# EtnaNode0_2.net
KiCad netlist of a schematic drawn in EAGLE
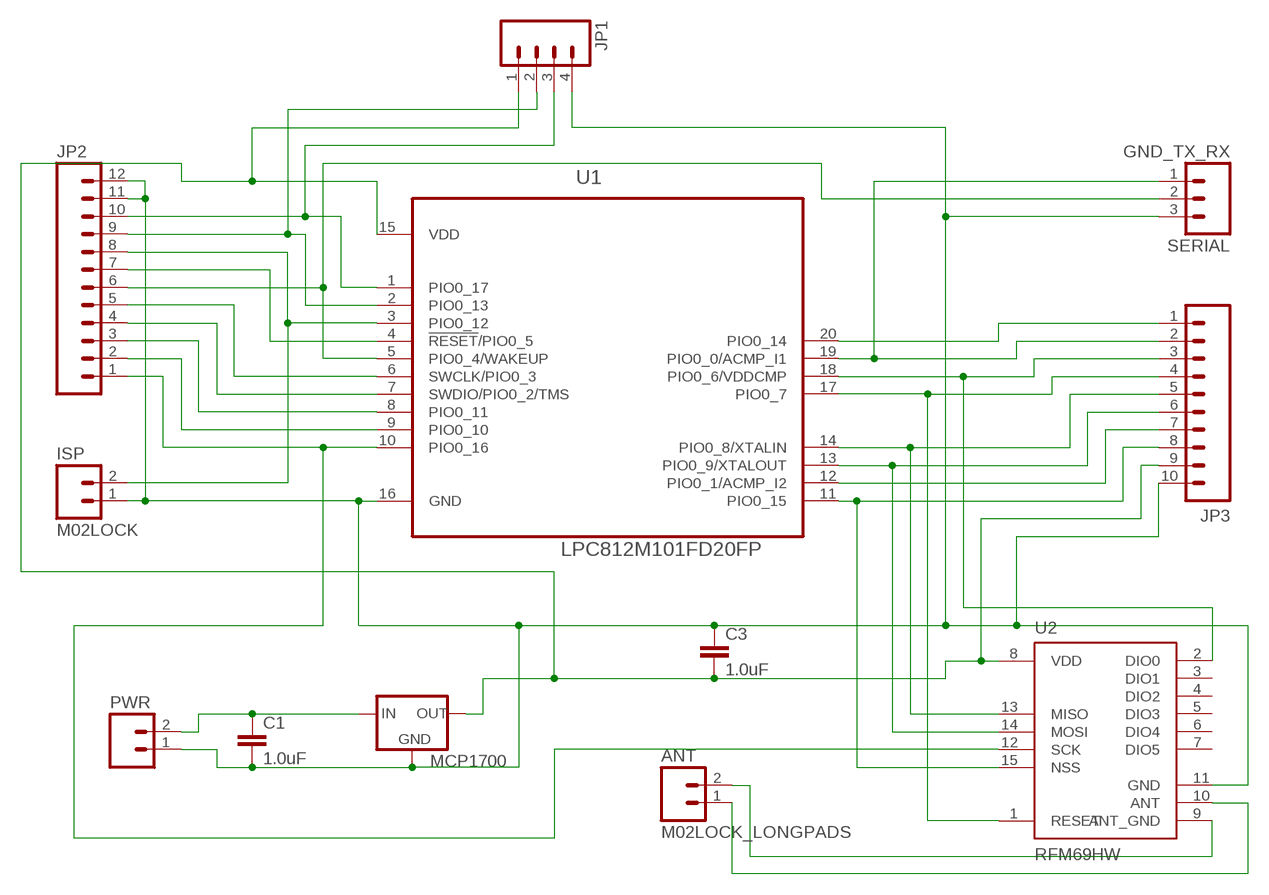
[diagram p0: schematic, sheet 1]

(export (version "E")
  (design (tool "Eeschema 10.0.6"))
  (components
    (comp (ref "ANT")
      (value "M02LOCK_LONGPADS")
      (footprint "eagle-import:1X02_LOCK_LONGPADS")
      (libsource (lib "eagle-import") (part "M02LOCK_LONGPADS"))
    )
    (comp (ref "C1")
      (value "1.0uF")
      (footprint "eagle-import:CAP-PTH-SMALL")
      (libsource (lib "eagle-import") (part "CAPPTH"))
    )
    (comp (ref "C3")
      (value "1.0uF")
      (footprint "eagle-import:CAP-PTH-SMALL")
      (libsource (lib "eagle-import") (part "CAPPTH"))
    )
    (comp (ref "ISP")
      (value "M02LOCK")
      (footprint "eagle-import:1X02_LOCK")
      (libsource (lib "eagle-import") (part "M02LOCK"))
    )
    (comp (ref "JP1")
      (value "M04LOCK")
      (footprint "eagle-import:1X04_LOCK")
      (libsource (lib "eagle-import") (part "M04LOCK"))
    )
    (comp (ref "JP2")
      (value "M12LOCK")
      (footprint "eagle-import:1X12_LOCK")
      (libsource (lib "eagle-import") (part "M12LOCK"))
    )
    (comp (ref "JP3")
      (value "M10LOCK")
      (footprint "eagle-import:1X10_LOCK")
      (libsource (lib "eagle-import") (part "M10LOCK"))
    )
    (comp (ref "MCP1700")
      (value "MCP1700INLINE")
      (footprint "eagle-import:TO92-INLINE")
      (libsource (lib "eagle-import") (part "MCP1700INLINE"))
    )
    (comp (ref "PWR")
      (value "M02LOCK_LONGPADS")
      (footprint "eagle-import:1X02_LOCK_LONGPADS")
      (libsource (lib "eagle-import") (part "M02LOCK_LONGPADS"))
    )
    (comp (ref "SERIAL")
      (value "GND_TX_RX")
      (footprint "eagle-import:1X03_LOCK")
      (libsource (lib "eagle-import") (part "M03LOCK"))
    )
    (comp (ref "U1")
      (value "LPC812M101FD20FP")
      (footprint "eagle-import:SOIC127P1032X265-20N")
      (libsource (lib "eagle-import") (part "LPC812M101FD20FP"))
    )
    (comp (ref "U2")
      (value "RFM69HW")
      (footprint "eagle-import:RFM69W-XXXS2")
      (libsource (lib "eagle-import") (part "RFM69HW"))
    )
  )
  (nets
    (net (code "1") (name "Net-(JP2-VCC)") (class "Default")
      (node (ref "C1") (pin "2") (pinfunction "2_2") (pintype "passive"))
      (node (ref "C3") (pin "1") (pinfunction "1_1") (pintype "passive"))
      (node (ref "ISP") (pin "1") (pinfunction "1_1") (pintype "passive"))
      (node (ref "JP1") (pin "4") (pinfunction "4_4") (pintype "passive"))
      (node (ref "JP2") (pin "11") (pinfunction "11_11") (pintype "passive"))
      (node (ref "JP2") (pin "12") (pinfunction "VCC_12") (pintype "passive"))
      (node (ref "JP3") (pin "10") (pinfunction "10_10") (pintype "passive"))
      (node (ref "MCP1700") (pin "1") (pinfunction "GND_1") (pintype "input"))
      (node (ref "PWR") (pin "1") (pinfunction "1_1") (pintype "passive"))
      (node (ref "SERIAL") (pin "3") (pinfunction "U0_RXD_3") (pintype "passive"))
      (node (ref "U1") (pin "16") (pinfunction "GND_16") (pintype "power_in"))
      (node (ref "U2") (pin "11") (pinfunction "GND_11") (pintype "power_in"))
    )
    (net (code "2") (name "Net-(MCP1700-IN)") (class "Default")
      (node (ref "C1") (pin "1") (pinfunction "1_1") (pintype "passive"))
      (node (ref "MCP1700") (pin "2") (pinfunction "IN_2") (pintype "input"))
      (node (ref "PWR") (pin "2") (pinfunction "2_2") (pintype "passive"))
    )
    (net (code "3") (name "Net-(MCP1700-OUT)") (class "Default")
      (node (ref "C3") (pin "2") (pinfunction "2_2") (pintype "passive"))
      (node (ref "JP1") (pin "1") (pinfunction "1_1") (pintype "passive"))
      (node (ref "JP3") (pin "9") (pinfunction "9_9") (pintype "passive"))
      (node (ref "MCP1700") (pin "3") (pinfunction "OUT_3") (pintype "passive"))
      (node (ref "U1") (pin "15") (pinfunction "VDD_15") (pintype "power_in"))
      (node (ref "U2") (pin "8") (pinfunction "VDD_8") (pintype "power_in"))
    )
    (net (code "4") (name "Net-(SERIAL-GND)") (class "Default")
      (node (ref "JP3") (pin "2") (pinfunction "2_2") (pintype "passive"))
      (node (ref "SERIAL") (pin "1") (pinfunction "GND_1") (pintype "passive"))
      (node (ref "U1") (pin "19") (pinfunction "PIO0_0/ACMP_I1_19") (pintype "bidirectional"))
    )
    (net (code "5") (name "Net-(SERIAL-U0_TXD)") (class "Default")
      (node (ref "JP2") (pin "6") (pinfunction "6_6") (pintype "passive"))
      (node (ref "SERIAL") (pin "2") (pinfunction "U0_TXD_2") (pintype "passive"))
      (node (ref "U1") (pin "5") (pinfunction "PIO0_4/WAKEUP_5") (pintype "bidirectional"))
    )
    (net (code "6") (name "Net-(U1-PIO0_1{slash}ACMP_I2)") (class "Default")
      (node (ref "JP3") (pin "7") (pinfunction "7_7") (pintype "passive"))
      (node (ref "U1") (pin "12") (pinfunction "PIO0_1/ACMP_I2_12") (pintype "bidirectional"))
    )
    (net (code "7") (name "Net-(U1-PIO0_6{slash}VDDCMP)") (class "Default")
      (node (ref "JP3") (pin "3") (pinfunction "3_3") (pintype "passive"))
      (node (ref "U1") (pin "18") (pinfunction "PIO0_6/VDDCMP_18") (pintype "bidirectional"))
      (node (ref "U2") (pin "2") (pinfunction "DIO0_2") (pintype "bidirectional"))
    )
    (net (code "8") (name "Net-(U1-PIO0_7)") (class "Default")
      (node (ref "JP3") (pin "4") (pinfunction "4_4") (pintype "passive"))
      (node (ref "U1") (pin "17") (pinfunction "PIO0_7_17") (pintype "bidirectional"))
      (node (ref "U2") (pin "1") (pinfunction "RESET_1") (pintype "input"))
    )
    (net (code "9") (name "Net-(U1-PIO0_8{slash}XTALIN)") (class "Default")
      (node (ref "JP3") (pin "5") (pinfunction "5_5") (pintype "passive"))
      (node (ref "U1") (pin "14") (pinfunction "PIO0_8/XTALIN_14") (pintype "bidirectional"))
      (node (ref "U2") (pin "13") (pinfunction "MISO_13") (pintype "bidirectional"))
    )
    (net (code "10") (name "Net-(U1-PIO0_9{slash}XTALOUT)") (class "Default")
      (node (ref "JP3") (pin "6") (pinfunction "6_6") (pintype "passive"))
      (node (ref "U1") (pin "13") (pinfunction "PIO0_9/XTALOUT_13") (pintype "bidirectional"))
      (node (ref "U2") (pin "14") (pinfunction "MOSI_14") (pintype "input"))
    )
    (net (code "11") (name "Net-(U1-PIO0_10)") (class "Default")
      (node (ref "JP2") (pin "2") (pinfunction "2_2") (pintype "passive"))
      (node (ref "U1") (pin "9") (pinfunction "PIO0_10_9") (pintype "input"))
    )
    (net (code "12") (name "Net-(U1-PIO0_11)") (class "Default")
      (node (ref "JP2") (pin "3") (pinfunction "3_3") (pintype "passive"))
      (node (ref "U1") (pin "8") (pinfunction "PIO0_11_8") (pintype "input"))
    )
    (net (code "13") (name "Net-(U1-PIO0_12)") (class "Default")
      (node (ref "ISP") (pin "2") (pinfunction "2_2") (pintype "passive"))
      (node (ref "JP2") (pin "8") (pinfunction "8_8") (pintype "passive"))
      (node (ref "U1") (pin "3") (pinfunction "PIO0_12_3") (pintype "bidirectional"))
    )
    (net (code "14") (name "Net-(U1-PIO0_13)") (class "Default")
      (node (ref "JP1") (pin "2") (pinfunction "2_2") (pintype "passive"))
      (node (ref "JP2") (pin "9") (pinfunction "9_9") (pintype "passive"))
      (node (ref "U1") (pin "2") (pinfunction "PIO0_13_2") (pintype "bidirectional"))
    )
    (net (code "15") (name "Net-(U1-PIO0_14)") (class "Default")
      (node (ref "JP3") (pin "1") (pinfunction "1_1") (pintype "passive"))
      (node (ref "U1") (pin "20") (pinfunction "PIO0_14_20") (pintype "bidirectional"))
    )
    (net (code "16") (name "Net-(U1-PIO0_15)") (class "Default")
      (node (ref "JP3") (pin "8") (pinfunction "8_8") (pintype "passive"))
      (node (ref "U1") (pin "11") (pinfunction "PIO0_15_11") (pintype "bidirectional"))
      (node (ref "U2") (pin "15") (pinfunction "NSS_15") (pintype "input"))
    )
    (net (code "17") (name "Net-(U1-PIO0_16)") (class "Default")
      (node (ref "JP2") (pin "1") (pinfunction "1_1") (pintype "passive"))
      (node (ref "U1") (pin "10") (pinfunction "PIO0_16_10") (pintype "bidirectional"))
      (node (ref "U2") (pin "12") (pinfunction "SCK_12") (pintype "input"))
    )
    (net (code "18") (name "Net-(U1-PIO0_17)") (class "Default")
      (node (ref "JP1") (pin "3") (pinfunction "3_3") (pintype "passive"))
      (node (ref "JP2") (pin "10") (pinfunction "10_10") (pintype "passive"))
      (node (ref "U1") (pin "1") (pinfunction "PIO0_17_1") (pintype "bidirectional"))
    )
    (net (code "19") (name "Net-(U1-SWCLK{slash}PIO0_3)") (class "Default")
      (node (ref "JP2") (pin "5") (pinfunction "5_5") (pintype "passive"))
      (node (ref "U1") (pin "6") (pinfunction "SWCLK/PIO0_3_6") (pintype "bidirectional"))
    )
    (net (code "20") (name "Net-(U1-SWDIO{slash}PIO0_2{slash}TMS)") (class "Default")
      (node (ref "JP2") (pin "4") (pinfunction "4_4") (pintype "passive"))
      (node (ref "U1") (pin "7") (pinfunction "SWDIO/PIO0_2/TMS_7") (pintype "bidirectional"))
    )
    (net (code "21") (name "Net-(U1-~{RESET}{slash}PIO0_5)") (class "Default")
      (node (ref "JP2") (pin "7") (pinfunction "7_7") (pintype "passive"))
      (node (ref "U1") (pin "4") (pinfunction "~{RESET}/PIO0_5_4") (pintype "bidirectional"))
    )
    (net (code "22") (name "Net-(U2-ANT)") (class "Default")
      (node (ref "ANT") (pin "1") (pinfunction "1_1") (pintype "passive"))
      (node (ref "U2") (pin "10") (pinfunction "ANT_10") (pintype "passive"))
    )
    (net (code "23") (name "Net-(U2-ANT_GND)") (class "Default")
      (node (ref "ANT") (pin "2") (pinfunction "2_2") (pintype "passive"))
      (node (ref "U2") (pin "9") (pinfunction "ANT_GND_9") (pintype "power_in"))
    )
    (net (code "24") (name "unconnected-(U2-DIO1-Pad3)") (class "Default")
      (node (ref "U2") (pin "3") (pinfunction "DIO1_3") (pintype "bidirectional"))
    )
    (net (code "25") (name "unconnected-(U2-DIO2-Pad4)") (class "Default")
      (node (ref "U2") (pin "4") (pinfunction "DIO2_4") (pintype "bidirectional"))
    )
    (net (code "26") (name "unconnected-(U2-DIO3-Pad5)") (class "Default")
      (node (ref "U2") (pin "5") (pinfunction "DIO3_5") (pintype "bidirectional"))
    )
    (net (code "27") (name "unconnected-(U2-DIO4-Pad6)") (class "Default")
      (node (ref "U2") (pin "6") (pinfunction "DIO4_6") (pintype "bidirectional"))
    )
    (net (code "28") (name "unconnected-(U2-DIO5-Pad7)") (class "Default")
      (node (ref "U2") (pin "7") (pinfunction "DIO5_7") (pintype "bidirectional"))
    )
  )
)
